# circuit.net
KiCad netlist of a schematic drawn in EAGLE
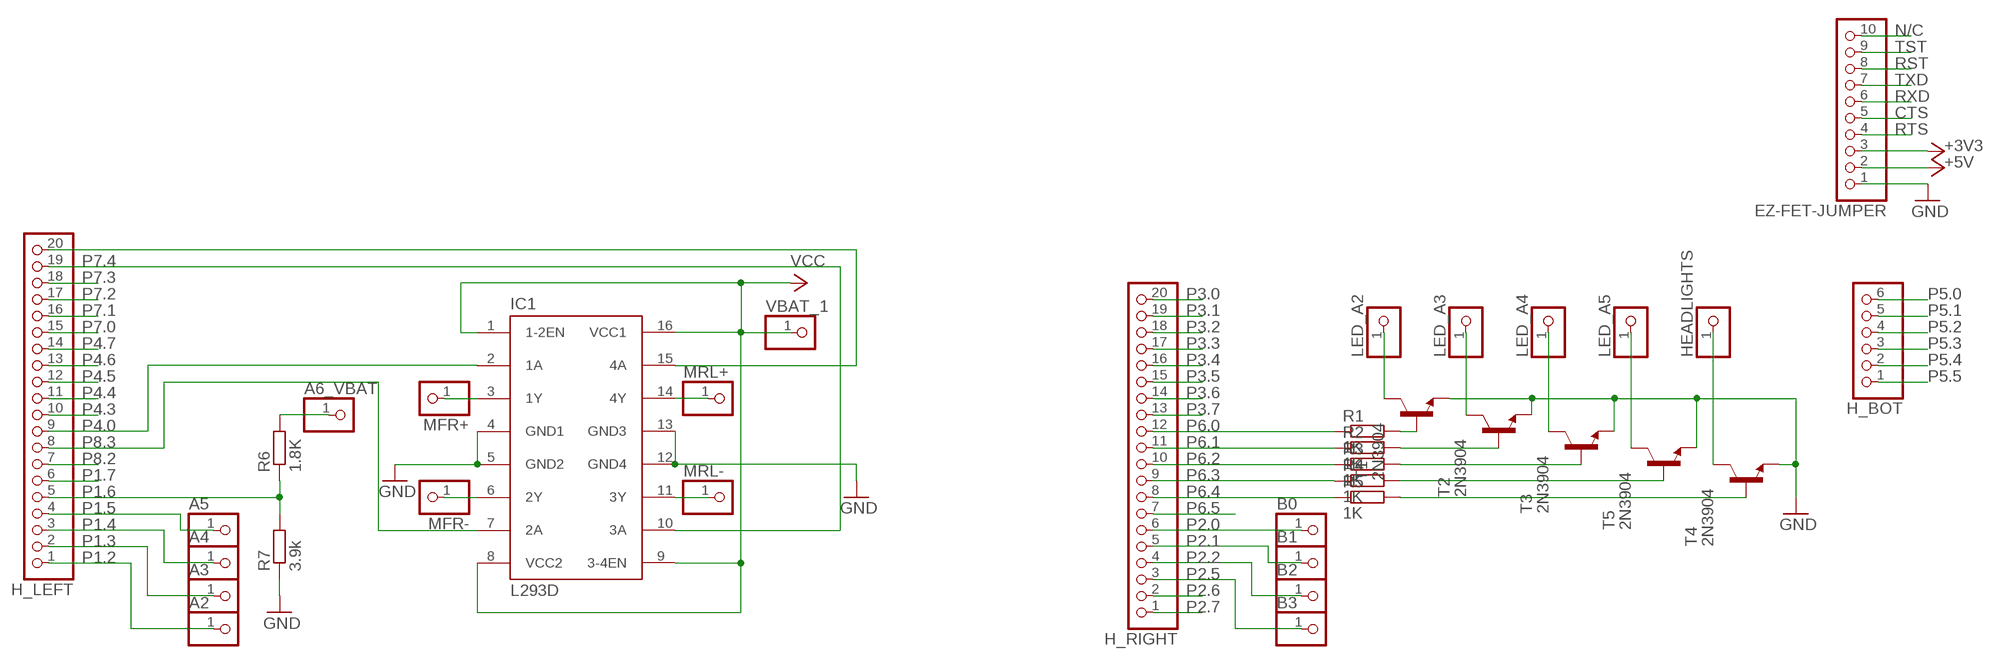
[diagram p0: schematic, sheet 1]

(export (version "E")
  (design (tool "Eeschema 10.0.6"))
  (components
    (comp (ref "A2")
      (value "PINHD-1X1")
      (footprint "eagle-import:1X01")
      (libsource (lib "eagle-import") (part "PINHD-1X1"))
    )
    (comp (ref "A3")
      (value "PINHD-1X1")
      (footprint "eagle-import:1X01")
      (libsource (lib "eagle-import") (part "PINHD-1X1"))
    )
    (comp (ref "A4")
      (value "PINHD-1X1")
      (footprint "eagle-import:1X01")
      (libsource (lib "eagle-import") (part "PINHD-1X1"))
    )
    (comp (ref "A5")
      (value "PINHD-1X1")
      (footprint "eagle-import:1X01")
      (libsource (lib "eagle-import") (part "PINHD-1X1"))
    )
    (comp (ref "A6_VBAT")
      (value "PINHD-1X1")
      (footprint "eagle-import:1X01")
      (libsource (lib "eagle-import") (part "PINHD-1X1"))
    )
    (comp (ref "B0")
      (value "PINHD-1X1")
      (footprint "eagle-import:1X01")
      (libsource (lib "eagle-import") (part "PINHD-1X1"))
    )
    (comp (ref "B1")
      (value "PINHD-1X1")
      (footprint "eagle-import:1X01")
      (libsource (lib "eagle-import") (part "PINHD-1X1"))
    )
    (comp (ref "B2")
      (value "PINHD-1X1")
      (footprint "eagle-import:1X01")
      (libsource (lib "eagle-import") (part "PINHD-1X1"))
    )
    (comp (ref "B3")
      (value "PINHD-1X1")
      (footprint "eagle-import:1X01")
      (libsource (lib "eagle-import") (part "PINHD-1X1"))
    )
    (comp (ref "EZ-FET-JUMPER")
      (value "PINHD-1X10")
      (footprint "eagle-import:1X10")
      (libsource (lib "eagle-import") (part "PINHD-1X10"))
    )
    (comp (ref "HEADLIGHTS")
      (value "PINHD-1X1")
      (footprint "eagle-import:1X01")
      (libsource (lib "eagle-import") (part "PINHD-1X1"))
    )
    (comp (ref "H_BOT")
      (value "PINHD-1X6")
      (footprint "eagle-import:1X06")
      (libsource (lib "eagle-import") (part "PINHD-1X6"))
    )
    (comp (ref "H_LEFT")
      (value "PINHD-1X20")
      (footprint "eagle-import:1X20")
      (libsource (lib "eagle-import") (part "PINHD-1X20"))
    )
    (comp (ref "H_RIGHT")
      (value "PINHD-1X20")
      (footprint "eagle-import:1X20")
      (libsource (lib "eagle-import") (part "PINHD-1X20"))
    )
    (comp (ref "IC1")
      (value "L293D")
      (footprint "eagle-import:DIL16")
      (libsource (lib "eagle-import") (part "L293D"))
    )
    (comp (ref "LED_A2")
      (value "PINHD-1X1")
      (footprint "eagle-import:1X01")
      (libsource (lib "eagle-import") (part "PINHD-1X1"))
    )
    (comp (ref "LED_A3")
      (value "PINHD-1X1")
      (footprint "eagle-import:1X01")
      (libsource (lib "eagle-import") (part "PINHD-1X1"))
    )
    (comp (ref "LED_A4")
      (value "PINHD-1X1")
      (footprint "eagle-import:1X01")
      (libsource (lib "eagle-import") (part "PINHD-1X1"))
    )
    (comp (ref "LED_A5")
      (value "PINHD-1X1")
      (footprint "eagle-import:1X01")
      (libsource (lib "eagle-import") (part "PINHD-1X1"))
    )
    (comp (ref "MFR+")
      (value "PINHD-1X1")
      (footprint "eagle-import:1X01")
      (libsource (lib "eagle-import") (part "PINHD-1X1"))
    )
    (comp (ref "MFR-")
      (value "PINHD-1X1")
      (footprint "eagle-import:1X01")
      (libsource (lib "eagle-import") (part "PINHD-1X1"))
    )
    (comp (ref "MRL+")
      (value "PINHD-1X1")
      (footprint "eagle-import:1X01")
      (libsource (lib "eagle-import") (part "PINHD-1X1"))
    )
    (comp (ref "MRL-")
      (value "PINHD-1X1")
      (footprint "eagle-import:1X01")
      (libsource (lib "eagle-import") (part "PINHD-1X1"))
    )
    (comp (ref "R1")
      (value "1K")
      (footprint "eagle-import:0207_7")
      (libsource (lib "eagle-import") (part "R-EU_0207/7"))
    )
    (comp (ref "R2")
      (value "1K")
      (footprint "eagle-import:0207_7")
      (libsource (lib "eagle-import") (part "R-EU_0207/7"))
    )
    (comp (ref "R3")
      (value "1K")
      (footprint "eagle-import:0207_7")
      (libsource (lib "eagle-import") (part "R-EU_0207/7"))
    )
    (comp (ref "R4")
      (value "1K")
      (footprint "eagle-import:0207_7")
      (libsource (lib "eagle-import") (part "R-EU_0207/7"))
    )
    (comp (ref "R5")
      (value "1K")
      (footprint "eagle-import:0207_7")
      (libsource (lib "eagle-import") (part "R-EU_0207/7"))
    )
    (comp (ref "R6")
      (value "1.8K")
      (footprint "eagle-import:0207_7")
      (libsource (lib "eagle-import") (part "R-EU_0207/7"))
    )
    (comp (ref "R7")
      (value "3.9k")
      (footprint "eagle-import:0207_7")
      (libsource (lib "eagle-import") (part "R-EU_0207/7"))
    )
    (comp (ref "T1")
      (value "2N3904")
      (footprint "eagle-import:TO92")
      (libsource (lib "eagle-import") (part "2N3904"))
    )
    (comp (ref "T2")
      (value "2N3904")
      (footprint "eagle-import:TO92")
      (libsource (lib "eagle-import") (part "2N3904"))
    )
    (comp (ref "T3")
      (value "2N3904")
      (footprint "eagle-import:TO92")
      (libsource (lib "eagle-import") (part "2N3904"))
    )
    (comp (ref "T4")
      (value "2N3904")
      (footprint "eagle-import:TO92")
      (libsource (lib "eagle-import") (part "2N3904"))
    )
    (comp (ref "T5")
      (value "2N3904")
      (footprint "eagle-import:TO92")
      (libsource (lib "eagle-import") (part "2N3904"))
    )
    (comp (ref "VBAT_1")
      (value "PINHD-1X1")
      (footprint "eagle-import:1X01")
      (libsource (lib "eagle-import") (part "PINHD-1X1"))
    )
  )
  (nets
    (net (code "1") (name "+3V3") (class "Default")
      (node (ref "EZ-FET-JUMPER") (pin "3") (pinfunction "3_3") (pintype "passive"))
    )
    (net (code "2") (name "+5V") (class "Default")
      (node (ref "EZ-FET-JUMPER") (pin "2") (pinfunction "2_2") (pintype "passive"))
    )
    (net (code "3") (name "/CTS") (class "Default")
      (node (ref "EZ-FET-JUMPER") (pin "5") (pinfunction "5_5") (pintype "passive"))
    )
    (net (code "4") (name "/N{slash}C") (class "Default")
      (node (ref "EZ-FET-JUMPER") (pin "10") (pinfunction "10_10") (pintype "passive"))
    )
    (net (code "5") (name "/P1.2") (class "Default")
      (node (ref "A2") (pin "1") (pinfunction "1_1") (pintype "passive"))
      (node (ref "H_LEFT") (pin "1") (pinfunction "1_1") (pintype "passive"))
    )
    (net (code "6") (name "/P1.3") (class "Default")
      (node (ref "A3") (pin "1") (pinfunction "1_1") (pintype "passive"))
      (node (ref "H_LEFT") (pin "2") (pinfunction "2_2") (pintype "passive"))
    )
    (net (code "7") (name "/P1.4") (class "Default")
      (node (ref "A4") (pin "1") (pinfunction "1_1") (pintype "passive"))
      (node (ref "H_LEFT") (pin "3") (pinfunction "3_3") (pintype "passive"))
    )
    (net (code "8") (name "/P1.5") (class "Default")
      (node (ref "A5") (pin "1") (pinfunction "1_1") (pintype "passive"))
      (node (ref "H_LEFT") (pin "4") (pinfunction "4_4") (pintype "passive"))
    )
    (net (code "9") (name "/P1.6") (class "Default")
      (node (ref "H_LEFT") (pin "5") (pinfunction "5_5") (pintype "passive"))
      (node (ref "R6") (pin "1") (pinfunction "1_1") (pintype "passive"))
      (node (ref "R7") (pin "2") (pinfunction "2_2") (pintype "passive"))
    )
    (net (code "10") (name "/P1.7") (class "Default")
      (node (ref "H_LEFT") (pin "6") (pinfunction "6_6") (pintype "passive"))
    )
    (net (code "11") (name "/P2.0") (class "Default")
      (node (ref "B0") (pin "1") (pinfunction "1_1") (pintype "passive"))
      (node (ref "H_RIGHT") (pin "6") (pinfunction "6_6") (pintype "passive"))
    )
    (net (code "12") (name "/P2.1") (class "Default")
      (node (ref "B1") (pin "1") (pinfunction "1_1") (pintype "passive"))
      (node (ref "H_RIGHT") (pin "5") (pinfunction "5_5") (pintype "passive"))
    )
    (net (code "13") (name "/P2.2") (class "Default")
      (node (ref "B2") (pin "1") (pinfunction "1_1") (pintype "passive"))
      (node (ref "H_RIGHT") (pin "4") (pinfunction "4_4") (pintype "passive"))
    )
    (net (code "14") (name "/P2.5") (class "Default")
      (node (ref "B3") (pin "1") (pinfunction "1_1") (pintype "passive"))
      (node (ref "H_RIGHT") (pin "3") (pinfunction "3_3") (pintype "passive"))
    )
    (net (code "15") (name "/P2.6") (class "Default")
      (node (ref "H_RIGHT") (pin "2") (pinfunction "2_2") (pintype "passive"))
    )
    (net (code "16") (name "/P2.7") (class "Default")
      (node (ref "H_RIGHT") (pin "1") (pinfunction "1_1") (pintype "passive"))
    )
    (net (code "17") (name "/P3.0") (class "Default")
      (node (ref "H_RIGHT") (pin "20") (pinfunction "20_20") (pintype "passive"))
    )
    (net (code "18") (name "/P3.1") (class "Default")
      (node (ref "H_RIGHT") (pin "19") (pinfunction "19_19") (pintype "passive"))
    )
    (net (code "19") (name "/P3.2") (class "Default")
      (node (ref "H_RIGHT") (pin "18") (pinfunction "18_18") (pintype "passive"))
    )
    (net (code "20") (name "/P3.3") (class "Default")
      (node (ref "H_RIGHT") (pin "17") (pinfunction "17_17") (pintype "passive"))
    )
    (net (code "21") (name "/P3.4") (class "Default")
      (node (ref "H_RIGHT") (pin "16") (pinfunction "16_16") (pintype "passive"))
    )
    (net (code "22") (name "/P3.5") (class "Default")
      (node (ref "H_RIGHT") (pin "15") (pinfunction "15_15") (pintype "passive"))
    )
    (net (code "23") (name "/P3.6") (class "Default")
      (node (ref "H_RIGHT") (pin "14") (pinfunction "14_14") (pintype "passive"))
    )
    (net (code "24") (name "/P3.7") (class "Default")
      (node (ref "H_RIGHT") (pin "13") (pinfunction "13_13") (pintype "passive"))
    )
    (net (code "25") (name "/P4.0") (class "Default")
      (node (ref "H_LEFT") (pin "9") (pinfunction "9_9") (pintype "passive"))
      (node (ref "IC1") (pin "2") (pinfunction "1A_2") (pintype "input"))
    )
    (net (code "26") (name "/P4.3") (class "Default")
      (node (ref "H_LEFT") (pin "10") (pinfunction "10_10") (pintype "passive"))
    )
    (net (code "27") (name "/P4.4") (class "Default")
      (node (ref "H_LEFT") (pin "11") (pinfunction "11_11") (pintype "passive"))
    )
    (net (code "28") (name "/P4.5") (class "Default")
      (node (ref "H_LEFT") (pin "12") (pinfunction "12_12") (pintype "passive"))
    )
    (net (code "29") (name "/P4.6") (class "Default")
      (node (ref "H_LEFT") (pin "13") (pinfunction "13_13") (pintype "passive"))
    )
    (net (code "30") (name "/P4.7") (class "Default")
      (node (ref "H_LEFT") (pin "14") (pinfunction "14_14") (pintype "passive"))
    )
    (net (code "31") (name "/P5.0") (class "Default")
      (node (ref "H_BOT") (pin "6") (pinfunction "6_6") (pintype "passive"))
    )
    (net (code "32") (name "/P5.1") (class "Default")
      (node (ref "H_BOT") (pin "5") (pinfunction "5_5") (pintype "passive"))
    )
    (net (code "33") (name "/P5.2") (class "Default")
      (node (ref "H_BOT") (pin "4") (pinfunction "4_4") (pintype "passive"))
    )
    (net (code "34") (name "/P5.3") (class "Default")
      (node (ref "H_BOT") (pin "3") (pinfunction "3_3") (pintype "passive"))
    )
    (net (code "35") (name "/P5.4") (class "Default")
      (node (ref "H_BOT") (pin "2") (pinfunction "2_2") (pintype "passive"))
    )
    (net (code "36") (name "/P5.5") (class "Default")
      (node (ref "H_BOT") (pin "1") (pinfunction "1_1") (pintype "passive"))
    )
    (net (code "37") (name "/P6.0") (class "Default")
      (node (ref "H_RIGHT") (pin "12") (pinfunction "12_12") (pintype "passive"))
      (node (ref "R1") (pin "1") (pinfunction "1_1") (pintype "passive"))
    )
    (net (code "38") (name "/P6.1") (class "Default")
      (node (ref "H_RIGHT") (pin "11") (pinfunction "11_11") (pintype "passive"))
      (node (ref "R2") (pin "1") (pinfunction "1_1") (pintype "passive"))
    )
    (net (code "39") (name "/P6.2") (class "Default")
      (node (ref "H_RIGHT") (pin "10") (pinfunction "10_10") (pintype "passive"))
      (node (ref "R3") (pin "1") (pinfunction "1_1") (pintype "passive"))
    )
    (net (code "40") (name "/P6.3") (class "Default")
      (node (ref "H_RIGHT") (pin "9") (pinfunction "9_9") (pintype "passive"))
      (node (ref "R4") (pin "1") (pinfunction "1_1") (pintype "passive"))
    )
    (net (code "41") (name "/P6.4") (class "Default")
      (node (ref "H_RIGHT") (pin "8") (pinfunction "8_8") (pintype "passive"))
      (node (ref "R5") (pin "1") (pinfunction "1_1") (pintype "passive"))
    )
    (net (code "42") (name "/P6.5") (class "Default")
      (node (ref "H_RIGHT") (pin "7") (pinfunction "7_7") (pintype "passive"))
    )
    (net (code "43") (name "/P7.0") (class "Default")
      (node (ref "H_LEFT") (pin "15") (pinfunction "15_15") (pintype "passive"))
    )
    (net (code "44") (name "/P7.1") (class "Default")
      (node (ref "H_LEFT") (pin "16") (pinfunction "16_16") (pintype "passive"))
    )
    (net (code "45") (name "/P7.2") (class "Default")
      (node (ref "H_LEFT") (pin "17") (pinfunction "17_17") (pintype "passive"))
    )
    (net (code "46") (name "/P7.3") (class "Default")
      (node (ref "H_LEFT") (pin "18") (pinfunction "18_18") (pintype "passive"))
    )
    (net (code "47") (name "/P7.4") (class "Default")
      (node (ref "H_LEFT") (pin "19") (pinfunction "19_19") (pintype "passive"))
      (node (ref "IC1") (pin "10") (pinfunction "3A_10") (pintype "input"))
    )
    (net (code "48") (name "/P8.2") (class "Default")
      (node (ref "H_LEFT") (pin "7") (pinfunction "7_7") (pintype "passive"))
    )
    (net (code "49") (name "/P8.3") (class "Default")
      (node (ref "H_LEFT") (pin "8") (pinfunction "8_8") (pintype "passive"))
      (node (ref "IC1") (pin "7") (pinfunction "2A_7") (pintype "input"))
    )
    (net (code "50") (name "/RST") (class "Default")
      (node (ref "EZ-FET-JUMPER") (pin "8") (pinfunction "8_8") (pintype "passive"))
    )
    (net (code "51") (name "/RTS") (class "Default")
      (node (ref "EZ-FET-JUMPER") (pin "4") (pinfunction "4_4") (pintype "passive"))
    )
    (net (code "52") (name "/RXD") (class "Default")
      (node (ref "EZ-FET-JUMPER") (pin "6") (pinfunction "6_6") (pintype "passive"))
    )
    (net (code "53") (name "/TST") (class "Default")
      (node (ref "EZ-FET-JUMPER") (pin "9") (pinfunction "9_9") (pintype "passive"))
    )
    (net (code "54") (name "/TXD") (class "Default")
      (node (ref "EZ-FET-JUMPER") (pin "7") (pinfunction "7_7") (pintype "passive"))
    )
    (net (code "55") (name "GND") (class "Default")
      (node (ref "EZ-FET-JUMPER") (pin "1") (pinfunction "1_1") (pintype "passive"))
      (node (ref "IC1") (pin "12") (pinfunction "GND4_12") (pintype "power_in"))
      (node (ref "IC1") (pin "13") (pinfunction "GND3_13") (pintype "power_in"))
      (node (ref "IC1") (pin "4") (pinfunction "GND1_4") (pintype "power_in"))
      (node (ref "IC1") (pin "5") (pinfunction "GND2_5") (pintype "power_in"))
      (node (ref "R7") (pin "1") (pinfunction "1_1") (pintype "passive"))
      (node (ref "T1") (pin "3") (pinfunction "E_3") (pintype "passive"))
      (node (ref "T2") (pin "3") (pinfunction "E_3") (pintype "passive"))
      (node (ref "T3") (pin "3") (pinfunction "E_3") (pintype "passive"))
      (node (ref "T4") (pin "3") (pinfunction "E_3") (pintype "passive"))
      (node (ref "T5") (pin "3") (pinfunction "E_3") (pintype "passive"))
    )
    (net (code "56") (name "Net-(A6_VBAT-Pad1)") (class "Default")
      (node (ref "A6_VBAT") (pin "1") (pinfunction "1_1") (pintype "passive"))
      (node (ref "R6") (pin "2") (pinfunction "2_2") (pintype "passive"))
    )
    (net (code "57") (name "Net-(IC1-1Y)") (class "Default")
      (node (ref "IC1") (pin "3") (pinfunction "1Y_3") (pintype "output"))
      (node (ref "MFR+") (pin "1") (pinfunction "1_1") (pintype "passive"))
    )
    (net (code "58") (name "Net-(IC1-2Y)") (class "Default")
      (node (ref "IC1") (pin "6") (pinfunction "2Y_6") (pintype "output"))
      (node (ref "MFR-") (pin "1") (pinfunction "1_1") (pintype "passive"))
    )
    (net (code "59") (name "Net-(IC1-3Y)") (class "Default")
      (node (ref "IC1") (pin "11") (pinfunction "3Y_11") (pintype "output"))
      (node (ref "MRL-") (pin "1") (pinfunction "1_1") (pintype "passive"))
    )
    (net (code "60") (name "Net-(IC1-4A)") (class "Default")
      (node (ref "H_LEFT") (pin "20") (pinfunction "20_20") (pintype "passive"))
      (node (ref "IC1") (pin "15") (pinfunction "4A_15") (pintype "input"))
    )
    (net (code "61") (name "Net-(IC1-4Y)") (class "Default")
      (node (ref "IC1") (pin "14") (pinfunction "4Y_14") (pintype "output"))
      (node (ref "MRL+") (pin "1") (pinfunction "1_1") (pintype "passive"))
    )
    (net (code "62") (name "Net-(T1-B)") (class "Default")
      (node (ref "R1") (pin "2") (pinfunction "2_2") (pintype "passive"))
      (node (ref "T1") (pin "2") (pinfunction "B_2") (pintype "passive"))
    )
    (net (code "63") (name "Net-(T1-C)") (class "Default")
      (node (ref "LED_A2") (pin "1") (pinfunction "1_1") (pintype "passive"))
      (node (ref "T1") (pin "1") (pinfunction "C_1") (pintype "passive"))
    )
    (net (code "64") (name "Net-(T2-B)") (class "Default")
      (node (ref "R2") (pin "2") (pinfunction "2_2") (pintype "passive"))
      (node (ref "T2") (pin "2") (pinfunction "B_2") (pintype "passive"))
    )
    (net (code "65") (name "Net-(T2-C)") (class "Default")
      (node (ref "LED_A3") (pin "1") (pinfunction "1_1") (pintype "passive"))
      (node (ref "T2") (pin "1") (pinfunction "C_1") (pintype "passive"))
    )
    (net (code "66") (name "Net-(T3-B)") (class "Default")
      (node (ref "R3") (pin "2") (pinfunction "2_2") (pintype "passive"))
      (node (ref "T3") (pin "2") (pinfunction "B_2") (pintype "passive"))
    )
    (net (code "67") (name "Net-(T3-C)") (class "Default")
      (node (ref "LED_A4") (pin "1") (pinfunction "1_1") (pintype "passive"))
      (node (ref "T3") (pin "1") (pinfunction "C_1") (pintype "passive"))
    )
    (net (code "68") (name "Net-(T4-B)") (class "Default")
      (node (ref "R5") (pin "2") (pinfunction "2_2") (pintype "passive"))
      (node (ref "T4") (pin "2") (pinfunction "B_2") (pintype "passive"))
    )
    (net (code "69") (name "Net-(T4-C)") (class "Default")
      (node (ref "HEADLIGHTS") (pin "1") (pinfunction "1_1") (pintype "passive"))
      (node (ref "T4") (pin "1") (pinfunction "C_1") (pintype "passive"))
    )
    (net (code "70") (name "Net-(T5-B)") (class "Default")
      (node (ref "R4") (pin "2") (pinfunction "2_2") (pintype "passive"))
      (node (ref "T5") (pin "2") (pinfunction "B_2") (pintype "passive"))
    )
    (net (code "71") (name "Net-(T5-C)") (class "Default")
      (node (ref "LED_A5") (pin "1") (pinfunction "1_1") (pintype "passive"))
      (node (ref "T5") (pin "1") (pinfunction "C_1") (pintype "passive"))
    )
    (net (code "72") (name "VCC") (class "Default")
      (node (ref "IC1") (pin "1") (pinfunction "1-2EN_1") (pintype "input"))
      (node (ref "IC1") (pin "16") (pinfunction "VCC1_16") (pintype "power_in"))
      (node (ref "IC1") (pin "8") (pinfunction "VCC2_8") (pintype "power_in"))
      (node (ref "IC1") (pin "9") (pinfunction "3-4EN_9") (pintype "input"))
      (node (ref "VBAT_1") (pin "1") (pinfunction "1_1") (pintype "passive"))
    )
  )
)
